# P1.net
KiCad netlist of a schematic drawn in Altium Designer
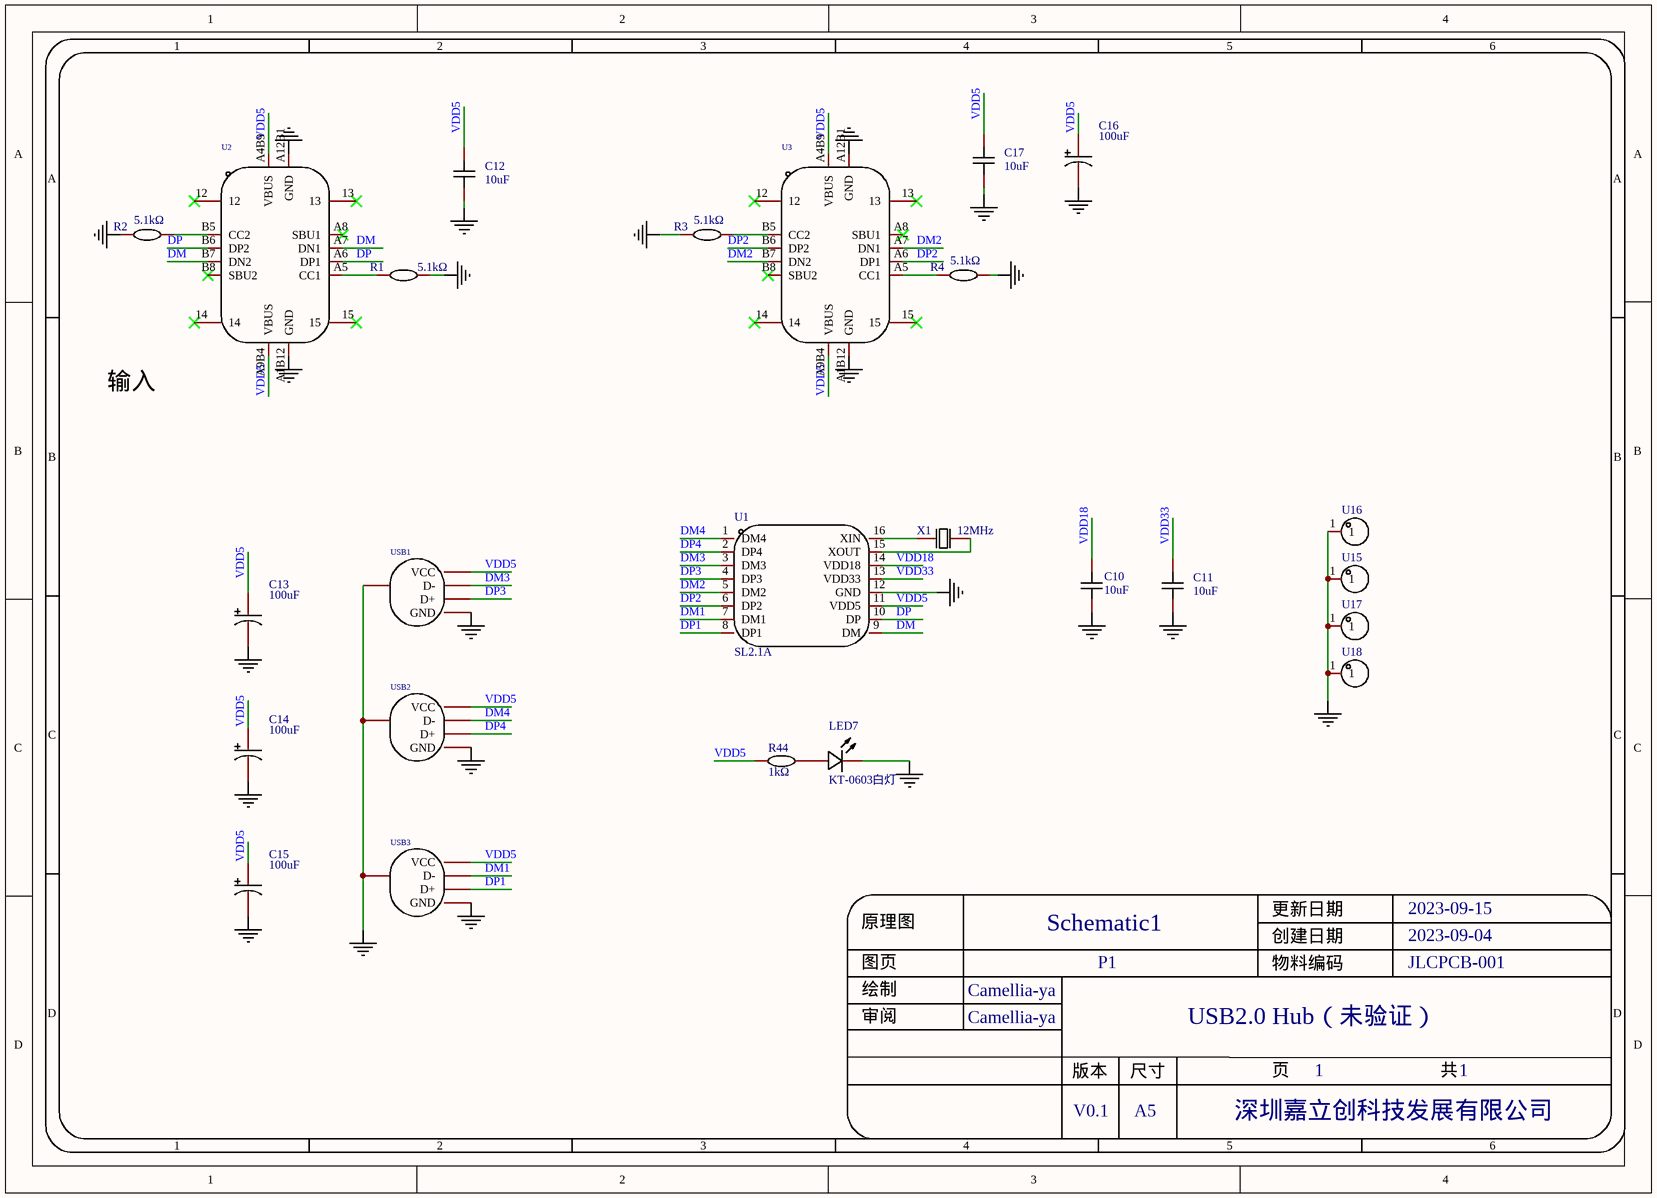
[diagram p0: P1.schdoc]

(export (version "E")
  (design (tool "Eeschema 10.0.6"))
  (components
    (comp (ref "C10")
      (value "10uF")
      (footprint "C0603")
      (description "容值:10uF;精度:±20%;额定电压:25V;材质(温度系数):X5R;")
      (fields
        (field (name "NAME") "10uF")
        (field (name "MANUFACTURER") "SAMSUNG(三星)")
        (field (name "MANUFACTURER PART") "CL10A106MA8NRNC")
      )
      (libsource (lib "1_P1") (part "CL10A106MA8NRNC"))
    )
    (comp (ref "C11")
      (value "10uF")
      (footprint "C0603")
      (description "容值:10uF;精度:±20%;额定电压:25V;材质(温度系数):X5R;")
      (fields
        (field (name "NAME") "10uF")
        (field (name "MANUFACTURER") "SAMSUNG(三星)")
        (field (name "MANUFACTURER PART") "CL10A106MA8NRNC")
      )
      (libsource (lib "1_P1") (part "CL10A106MA8NRNC"))
    )
    (comp (ref "C12")
      (value "10uF")
      (footprint "C0603")
      (description "容值:10uF;精度:±20%;额定电压:25V;材质(温度系数):X5R;")
      (fields
        (field (name "NAME") "10uF")
        (field (name "MANUFACTURER") "SAMSUNG(三星)")
        (field (name "MANUFACTURER PART") "CL10A106MA8NRNC")
      )
      (libsource (lib "1_P1") (part "CL10A106MA8NRNC"))
    )
    (comp (ref "C13")
      (value "100uF")
      (footprint "CAP-SMD_BD8.0-L8.3-W8.3-LS9.0-FD")
      (description "容值:100uF;精度:±20%;额定电压:25V;纹波电流:-;等效串联电阻:-;")
      (fields
        (field (name "NAME") "100uF")
        (field (name "MANUFACTURER") "lelon(立隆)")
        (field (name "MANUFACTURER PART") "VZH101M1ETR-0806")
      )
      (libsource (lib "1_P1") (part "VZH101M1ETR-0806"))
    )
    (comp (ref "C14")
      (value "100uF")
      (footprint "CAP-SMD_BD8.0-L8.3-W8.3-LS9.0-FD")
      (description "容值:100uF;精度:±20%;额定电压:25V;纹波电流:-;等效串联电阻:-;")
      (fields
        (field (name "NAME") "100uF")
        (field (name "MANUFACTURER") "lelon(立隆)")
        (field (name "MANUFACTURER PART") "VZH101M1ETR-0806")
      )
      (libsource (lib "1_P1") (part "VZH101M1ETR-0806"))
    )
    (comp (ref "C15")
      (value "100uF")
      (footprint "CAP-SMD_BD8.0-L8.3-W8.3-LS9.0-FD")
      (description "容值:100uF;精度:±20%;额定电压:25V;纹波电流:-;等效串联电阻:-;")
      (fields
        (field (name "NAME") "100uF")
        (field (name "MANUFACTURER") "lelon(立隆)")
        (field (name "MANUFACTURER PART") "VZH101M1ETR-0806")
      )
      (libsource (lib "1_P1") (part "VZH101M1ETR-0806"))
    )
    (comp (ref "C16")
      (value "100uF")
      (footprint "CAP-SMD_BD8.0-L8.3-W8.3-LS9.0-FD")
      (description "容值:100uF;精度:±20%;额定电压:25V;纹波电流:-;等效串联电阻:-;")
      (fields
        (field (name "NAME") "100uF")
        (field (name "MANUFACTURER") "lelon(立隆)")
        (field (name "MANUFACTURER PART") "VZH101M1ETR-0806")
      )
      (libsource (lib "1_P1") (part "VZH101M1ETR-0806"))
    )
    (comp (ref "C17")
      (value "10uF")
      (footprint "C0603")
      (description "容值:10uF;精度:±20%;额定电压:25V;材质(温度系数):X5R;")
      (fields
        (field (name "NAME") "10uF")
        (field (name "MANUFACTURER") "SAMSUNG(三星)")
        (field (name "MANUFACTURER PART") "CL10A106MA8NRNC")
      )
      (libsource (lib "1_P1") (part "CL10A106MA8NRNC"))
    )
    (comp (ref "LED7")
      (value "KT-0603白灯")
      (footprint "LED0603-R-RD_WHITE")
      (description "发光颜色:白灯;")
      (fields (field (name "NAME") "KT-0603白灯") (field (name "MANUFACTURER") "KENTO"))
      (libsource (lib "1_P1") (part "KT-0603白灯"))
    )
    (comp (ref "R1")
      (value "5.1kΩ")
      (footprint "R0603")
      (description "电阻类型:厚膜电阻;阻值:5.1kΩ;精度:±1%;功率:100mW;温度系数:±100ppm/℃;最大工作电压:75V;工作温度范围:-55℃~+155℃;")
      (fields
        (field (name "NAME") "5.1kΩ")
        (field (name "MANUFACTURER") "UNI-ROYAL(厚声)")
        (field (name "MANUFACTURER PART") "0603WAF5101T5E")
      )
      (libsource (lib "1_P1") (part "0603WAF5101T5E"))
    )
    (comp (ref "R2")
      (value "5.1kΩ")
      (footprint "R0603")
      (description "电阻类型:厚膜电阻;阻值:5.1kΩ;精度:±1%;功率:100mW;温度系数:±100ppm/℃;最大工作电压:75V;工作温度范围:-55℃~+155℃;")
      (fields
        (field (name "NAME") "5.1kΩ")
        (field (name "MANUFACTURER") "UNI-ROYAL(厚声)")
        (field (name "MANUFACTURER PART") "0603WAF5101T5E")
      )
      (libsource (lib "1_P1") (part "0603WAF5101T5E"))
    )
    (comp (ref "R3")
      (value "5.1kΩ")
      (footprint "R0603")
      (description "电阻类型:厚膜电阻;阻值:5.1kΩ;精度:±1%;功率:100mW;温度系数:±100ppm/℃;最大工作电压:75V;工作温度范围:-55℃~+155℃;")
      (fields
        (field (name "NAME") "5.1kΩ")
        (field (name "MANUFACTURER") "UNI-ROYAL(厚声)")
        (field (name "MANUFACTURER PART") "0603WAF5101T5E")
      )
      (libsource (lib "1_P1") (part "0603WAF5101T5E"))
    )
    (comp (ref "R4")
      (value "5.1kΩ")
      (footprint "R0603")
      (description "电阻类型:厚膜电阻;阻值:5.1kΩ;精度:±1%;功率:100mW;温度系数:±100ppm/℃;最大工作电压:75V;工作温度范围:-55℃~+155℃;")
      (fields
        (field (name "NAME") "5.1kΩ")
        (field (name "MANUFACTURER") "UNI-ROYAL(厚声)")
        (field (name "MANUFACTURER PART") "0603WAF5101T5E")
      )
      (libsource (lib "1_P1") (part "0603WAF5101T5E"))
    )
    (comp (ref "R44")
      (value "1kΩ")
      (footprint "R0603")
      (description "电阻类型:厚膜电阻;阻值:1kΩ;精度:±1%;功率:100mW;")
      (fields
        (field (name "NAME") "1kΩ")
        (field (name "MANUFACTURER") "UNI-ROYAL(厚声)")
        (field (name "MANUFACTURER PART") "0603WAF1001T5E")
      )
      (libsource (lib "1_P1") (part "0603WAF1001T5E"))
    )
    (comp (ref "U1")
      (value "SL2.1A")
      (footprint "SOP-16_L10.0-W3.9-P1.27-LS6.0-BL")
      (description "应用功能:集线器;接口协议:-;")
      (fields (field (name "NAME") "SL2.1A") (field (name "MANUFACTURER") "CoreChips(和芯润德)"))
      (libsource (lib "1_P1") (part "SL2.1A"))
    )
    (comp (ref "U2")
      (value "YTC-TC16-273A1")
      (footprint "TYPE-C-SMD_YIYUAN_YTC-TC16-273A1")
      (description "连接器类型:Type-C;公母:母座;触点数量:16;")
      (fields (field (name "MANUFACTURER") "YIYUAN(怡远)"))
      (libsource (lib "1_P1") (part "YTC-TC16-273A1"))
    )
    (comp (ref "U3")
      (value "YTC-TC16-273A1")
      (footprint "TYPE-C-SMD_YIYUAN_YTC-TC16-273A1")
      (description "连接器类型:Type-C;公母:母座;触点数量:16;")
      (fields (field (name "MANUFACTURER") "YIYUAN(怡远)"))
      (libsource (lib "1_P1") (part "YTC-TC16-273A1"))
    )
    (comp (ref "U15")
      (value "铜柱M3*12+3")
      (footprint "TH_BD4.7-D3.0")
      (fields (field (name "MANUFACTURER") "国产"))
      (libsource (lib "1_P1") (part "铜柱M3*12+3"))
    )
    (comp (ref "U16")
      (value "铜柱M3*12+3")
      (footprint "TH_BD4.7-D3.0")
      (fields (field (name "MANUFACTURER") "国产"))
      (libsource (lib "1_P1") (part "铜柱M3*12+3"))
    )
    (comp (ref "U17")
      (value "铜柱M3*12+3")
      (footprint "TH_BD4.7-D3.0")
      (fields (field (name "MANUFACTURER") "国产"))
      (libsource (lib "1_P1") (part "铜柱M3*12+3"))
    )
    (comp (ref "U18")
      (value "铜柱M3*12+3")
      (footprint "TH_BD4.7-D3.0")
      (fields (field (name "MANUFACTURER") "国产"))
      (libsource (lib "1_P1") (part "铜柱M3*12+3"))
    )
    (comp (ref "USB1")
      (value "AF 90° WJDG")
      (footprint "USB-A-TH_AF-WJDG")
      (description "连接器类型:Type-A;标准:USB 2.0;公母:母座;触点数量:4;端口数量:1;安装方式:弯插;额定电流 - 电源:1.5A;工作温度范围:-25℃~+85℃;")
      (fields (field (name "MANUFACTURER") "SHOU HAN(首韩)"))
      (libsource (lib "1_P1") (part "AF 90° WJDG"))
    )
    (comp (ref "USB2")
      (value "AF 90° WJDG")
      (footprint "USB-A-TH_AF-WJDG")
      (description "连接器类型:Type-A;标准:USB 2.0;公母:母座;触点数量:4;端口数量:1;安装方式:弯插;额定电流 - 电源:1.5A;工作温度范围:-25℃~+85℃;")
      (fields (field (name "MANUFACTURER") "SHOU HAN(首韩)"))
      (libsource (lib "1_P1") (part "AF 90° WJDG"))
    )
    (comp (ref "USB3")
      (value "AF 90° WJDG")
      (footprint "USB-A-TH_AF-WJDG")
      (description "连接器类型:Type-A;标准:USB 2.0;公母:母座;触点数量:4;端口数量:1;安装方式:弯插;额定电流 - 电源:1.5A;工作温度范围:-25℃~+85℃;")
      (fields (field (name "MANUFACTURER") "SHOU HAN(首韩)"))
      (libsource (lib "1_P1") (part "AF 90° WJDG"))
    )
    (comp (ref "X1")
      (value "12MHz")
      (footprint "HC-49US_L11.5-W4.5-P4.88")
      (description "频率:12MHz;频率公差:±20ppm;负载电容:20pF;")
      (fields
        (field (name "NAME") "12MHz")
        (field (name "MANUFACTURER") "YXC(扬兴晶振)")
        (field (name "MANUFACTURER PART") "X49SD12MSD2SI")
      )
      (libsource (lib "1_P1") (part "X49SD12MSD2SI"))
    )
  )
  (nets
    (net (code "1") (name "/DM") (class "Default")
      (node (ref "U1") (pin "9") (pinfunction "DM_9") (pintype "passive"))
      (node (ref "U2") (pin "A7") (pinfunction "DN1_A7") (pintype "passive"))
      (node (ref "U2") (pin "B7") (pinfunction "DN2_B7") (pintype "passive"))
    )
    (net (code "2") (name "/DM1") (class "Default")
      (node (ref "U1") (pin "7") (pinfunction "DM1_7") (pintype "passive"))
      (node (ref "USB3") (pin "2") (pinfunction "D-_2") (pintype "passive"))
    )
    (net (code "3") (name "/DM2") (class "Default")
      (node (ref "U1") (pin "5") (pinfunction "DM2_5") (pintype "passive"))
      (node (ref "U3") (pin "A7") (pinfunction "DN1_A7") (pintype "passive"))
      (node (ref "U3") (pin "B7") (pinfunction "DN2_B7") (pintype "passive"))
    )
    (net (code "4") (name "/DM3") (class "Default")
      (node (ref "U1") (pin "3") (pinfunction "DM3_3") (pintype "passive"))
      (node (ref "USB1") (pin "2") (pinfunction "D-_2") (pintype "passive"))
    )
    (net (code "5") (name "/DM4") (class "Default")
      (node (ref "U1") (pin "1") (pinfunction "DM4_1") (pintype "passive"))
      (node (ref "USB2") (pin "2") (pinfunction "D-_2") (pintype "passive"))
    )
    (net (code "6") (name "/DP") (class "Default")
      (node (ref "U1") (pin "10") (pinfunction "DP_10") (pintype "passive"))
      (node (ref "U2") (pin "A6") (pinfunction "DP1_A6") (pintype "passive"))
      (node (ref "U2") (pin "B6") (pinfunction "DP2_B6") (pintype "passive"))
    )
    (net (code "7") (name "/DP1") (class "Default")
      (node (ref "U1") (pin "8") (pinfunction "DP1_8") (pintype "passive"))
      (node (ref "USB3") (pin "3") (pinfunction "D+_3") (pintype "passive"))
    )
    (net (code "8") (name "/DP2") (class "Default")
      (node (ref "U1") (pin "6") (pinfunction "DP2_6") (pintype "passive"))
      (node (ref "U3") (pin "A6") (pinfunction "DP1_A6") (pintype "passive"))
      (node (ref "U3") (pin "B6") (pinfunction "DP2_B6") (pintype "passive"))
    )
    (net (code "9") (name "/DP3") (class "Default")
      (node (ref "U1") (pin "4") (pinfunction "DP3_4") (pintype "passive"))
      (node (ref "USB1") (pin "3") (pinfunction "D+_3") (pintype "passive"))
    )
    (net (code "10") (name "/DP4") (class "Default")
      (node (ref "U1") (pin "2") (pinfunction "DP4_2") (pintype "passive"))
      (node (ref "USB2") (pin "3") (pinfunction "D+_3") (pintype "passive"))
    )
    (net (code "11") (name "/VDD5") (class "Default")
      (node (ref "C12") (pin "1") (pinfunction "1_1") (pintype "passive"))
      (node (ref "C13") (pin "1") (pinfunction "1_1") (pintype "passive"))
      (node (ref "C14") (pin "1") (pinfunction "1_1") (pintype "passive"))
      (node (ref "C15") (pin "1") (pinfunction "1_1") (pintype "passive"))
      (node (ref "C16") (pin "1") (pinfunction "1_1") (pintype "passive"))
      (node (ref "C17") (pin "1") (pinfunction "1_1") (pintype "passive"))
      (node (ref "R44") (pin "2") (pinfunction "2_2") (pintype "passive"))
      (node (ref "U1") (pin "11") (pinfunction "VDD5_11") (pintype "passive"))
      (node (ref "U2") (pin "A4B9") (pinfunction "VBUS_A4B9") (pintype "passive"))
      (node (ref "U2") (pin "A9B4") (pinfunction "VBUS_A9B4") (pintype "passive"))
      (node (ref "U3") (pin "A4B9") (pinfunction "VBUS_A4B9") (pintype "passive"))
      (node (ref "U3") (pin "A9B4") (pinfunction "VBUS_A9B4") (pintype "passive"))
      (node (ref "USB1") (pin "1") (pinfunction "VCC_1") (pintype "passive"))
      (node (ref "USB2") (pin "1") (pinfunction "VCC_1") (pintype "passive"))
      (node (ref "USB3") (pin "1") (pinfunction "VCC_1") (pintype "passive"))
    )
    (net (code "12") (name "/VDD18") (class "Default")
      (node (ref "C10") (pin "2") (pinfunction "2_2") (pintype "passive"))
      (node (ref "U1") (pin "14") (pinfunction "VDD18_14") (pintype "passive"))
    )
    (net (code "13") (name "/VDD33") (class "Default")
      (node (ref "C11") (pin "1") (pinfunction "1_1") (pintype "passive"))
      (node (ref "U1") (pin "13") (pinfunction "VDD33_13") (pintype "passive"))
    )
    (net (code "14") (name "<NO NET>") (class "Default")
      (node (ref "C10") (pin "1") (pinfunction "1_1") (pintype "passive"))
      (node (ref "C11") (pin "2") (pinfunction "2_2") (pintype "passive"))
      (node (ref "C12") (pin "2") (pinfunction "2_2") (pintype "passive"))
      (node (ref "C13") (pin "2") (pinfunction "2_2") (pintype "passive"))
      (node (ref "C14") (pin "2") (pinfunction "2_2") (pintype "passive"))
      (node (ref "C15") (pin "2") (pinfunction "2_2") (pintype "passive"))
      (node (ref "C16") (pin "2") (pinfunction "2_2") (pintype "passive"))
      (node (ref "C17") (pin "2") (pinfunction "2_2") (pintype "passive"))
      (node (ref "LED7") (pin "2") (pinfunction "K_2") (pintype "passive"))
      (node (ref "R1") (pin "1") (pinfunction "1_1") (pintype "passive"))
      (node (ref "R2") (pin "2") (pinfunction "2_2") (pintype "passive"))
      (node (ref "R3") (pin "2") (pinfunction "2_2") (pintype "passive"))
      (node (ref "R4") (pin "1") (pinfunction "1_1") (pintype "passive"))
      (node (ref "U1") (pin "12") (pinfunction "GND_12") (pintype "passive"))
      (node (ref "U15") (pin "1") (pinfunction "1_1") (pintype "passive"))
      (node (ref "U16") (pin "1") (pinfunction "1_1") (pintype "passive"))
      (node (ref "U17") (pin "1") (pinfunction "1_1") (pintype "passive"))
      (node (ref "U18") (pin "1") (pinfunction "1_1") (pintype "passive"))
      (node (ref "U2") (pin "A12B1") (pinfunction "GND_A12B1") (pintype "passive"))
      (node (ref "U2") (pin "A1B12") (pinfunction "GND_A1B12") (pintype "passive"))
      (node (ref "U3") (pin "A12B1") (pinfunction "GND_A12B1") (pintype "passive"))
      (node (ref "U3") (pin "A1B12") (pinfunction "GND_A1B12") (pintype "passive"))
      (node (ref "USB1") (pin "4") (pinfunction "GND_4") (pintype "passive"))
      (node (ref "USB1") (pin "5") (pinfunction "SHLD_5") (pintype "passive"))
      (node (ref "USB2") (pin "4") (pinfunction "GND_4") (pintype "passive"))
      (node (ref "USB2") (pin "5") (pinfunction "SHLD_5") (pintype "passive"))
      (node (ref "USB3") (pin "4") (pinfunction "GND_4") (pintype "passive"))
      (node (ref "USB3") (pin "5") (pinfunction "SHLD_5") (pintype "passive"))
    )
    (net (code "15") (name "Net-(LED7-A)") (class "Default")
      (node (ref "LED7") (pin "1") (pinfunction "A_1") (pintype "passive"))
      (node (ref "R44") (pin "1") (pinfunction "1_1") (pintype "passive"))
    )
    (net (code "16") (name "Net-(U1-XIN)") (class "Default")
      (node (ref "U1") (pin "16") (pinfunction "XIN_16") (pintype "passive"))
      (node (ref "X1") (pin "1") (pinfunction "OSC1_1") (pintype "passive"))
    )
    (net (code "17") (name "Net-(U1-XOUT)") (class "Default")
      (node (ref "U1") (pin "15") (pinfunction "XOUT_15") (pintype "passive"))
      (node (ref "X1") (pin "2") (pinfunction "OSC2_2") (pintype "passive"))
    )
    (net (code "18") (name "Net-(U2-CC1)") (class "Default")
      (node (ref "R1") (pin "2") (pinfunction "2_2") (pintype "passive"))
      (node (ref "U2") (pin "A5") (pinfunction "CC1_A5") (pintype "passive"))
    )
    (net (code "19") (name "Net-(U2-CC2)") (class "Default")
      (node (ref "R2") (pin "1") (pinfunction "1_1") (pintype "passive"))
      (node (ref "U2") (pin "B5") (pinfunction "CC2_B5") (pintype "passive"))
    )
    (net (code "20") (name "Net-(U3-CC1)") (class "Default")
      (node (ref "R4") (pin "2") (pinfunction "2_2") (pintype "passive"))
      (node (ref "U3") (pin "A5") (pinfunction "CC1_A5") (pintype "passive"))
    )
    (net (code "21") (name "Net-(U3-CC2)") (class "Default")
      (node (ref "R3") (pin "1") (pinfunction "1_1") (pintype "passive"))
      (node (ref "U3") (pin "B5") (pinfunction "CC2_B5") (pintype "passive"))
    )
    (net (code "22") (name "unconnected-(U2-Pad12)") (class "Default")
      (node (ref "U2") (pin "12") (pinfunction "12_12") (pintype "passive+no_connect"))
    )
    (net (code "23") (name "unconnected-(U2-Pad13)") (class "Default")
      (node (ref "U2") (pin "13") (pinfunction "13_13") (pintype "passive+no_connect"))
    )
    (net (code "24") (name "unconnected-(U2-Pad14)") (class "Default")
      (node (ref "U2") (pin "14") (pinfunction "14_14") (pintype "passive+no_connect"))
    )
    (net (code "25") (name "unconnected-(U2-Pad15)") (class "Default")
      (node (ref "U2") (pin "15") (pinfunction "15_15") (pintype "passive+no_connect"))
    )
    (net (code "26") (name "unconnected-(U2-SBU1-PadA8)") (class "Default")
      (node (ref "U2") (pin "A8") (pinfunction "SBU1_A8") (pintype "passive+no_connect"))
    )
    (net (code "27") (name "unconnected-(U2-SBU2-PadB8)") (class "Default")
      (node (ref "U2") (pin "B8") (pinfunction "SBU2_B8") (pintype "passive+no_connect"))
    )
    (net (code "28") (name "unconnected-(U3-Pad12)") (class "Default")
      (node (ref "U3") (pin "12") (pinfunction "12_12") (pintype "passive+no_connect"))
    )
    (net (code "29") (name "unconnected-(U3-Pad13)") (class "Default")
      (node (ref "U3") (pin "13") (pinfunction "13_13") (pintype "passive+no_connect"))
    )
    (net (code "30") (name "unconnected-(U3-Pad14)") (class "Default")
      (node (ref "U3") (pin "14") (pinfunction "14_14") (pintype "passive+no_connect"))
    )
    (net (code "31") (name "unconnected-(U3-Pad15)") (class "Default")
      (node (ref "U3") (pin "15") (pinfunction "15_15") (pintype "passive+no_connect"))
    )
    (net (code "32") (name "unconnected-(U3-SBU1-PadA8)") (class "Default")
      (node (ref "U3") (pin "A8") (pinfunction "SBU1_A8") (pintype "passive+no_connect"))
    )
    (net (code "33") (name "unconnected-(U3-SBU2-PadB8)") (class "Default")
      (node (ref "U3") (pin "B8") (pinfunction "SBU2_B8") (pintype "passive+no_connect"))
    )
  )
)
